# julia_v2.net
KiCad netlist of a schematic drawn in EAGLE
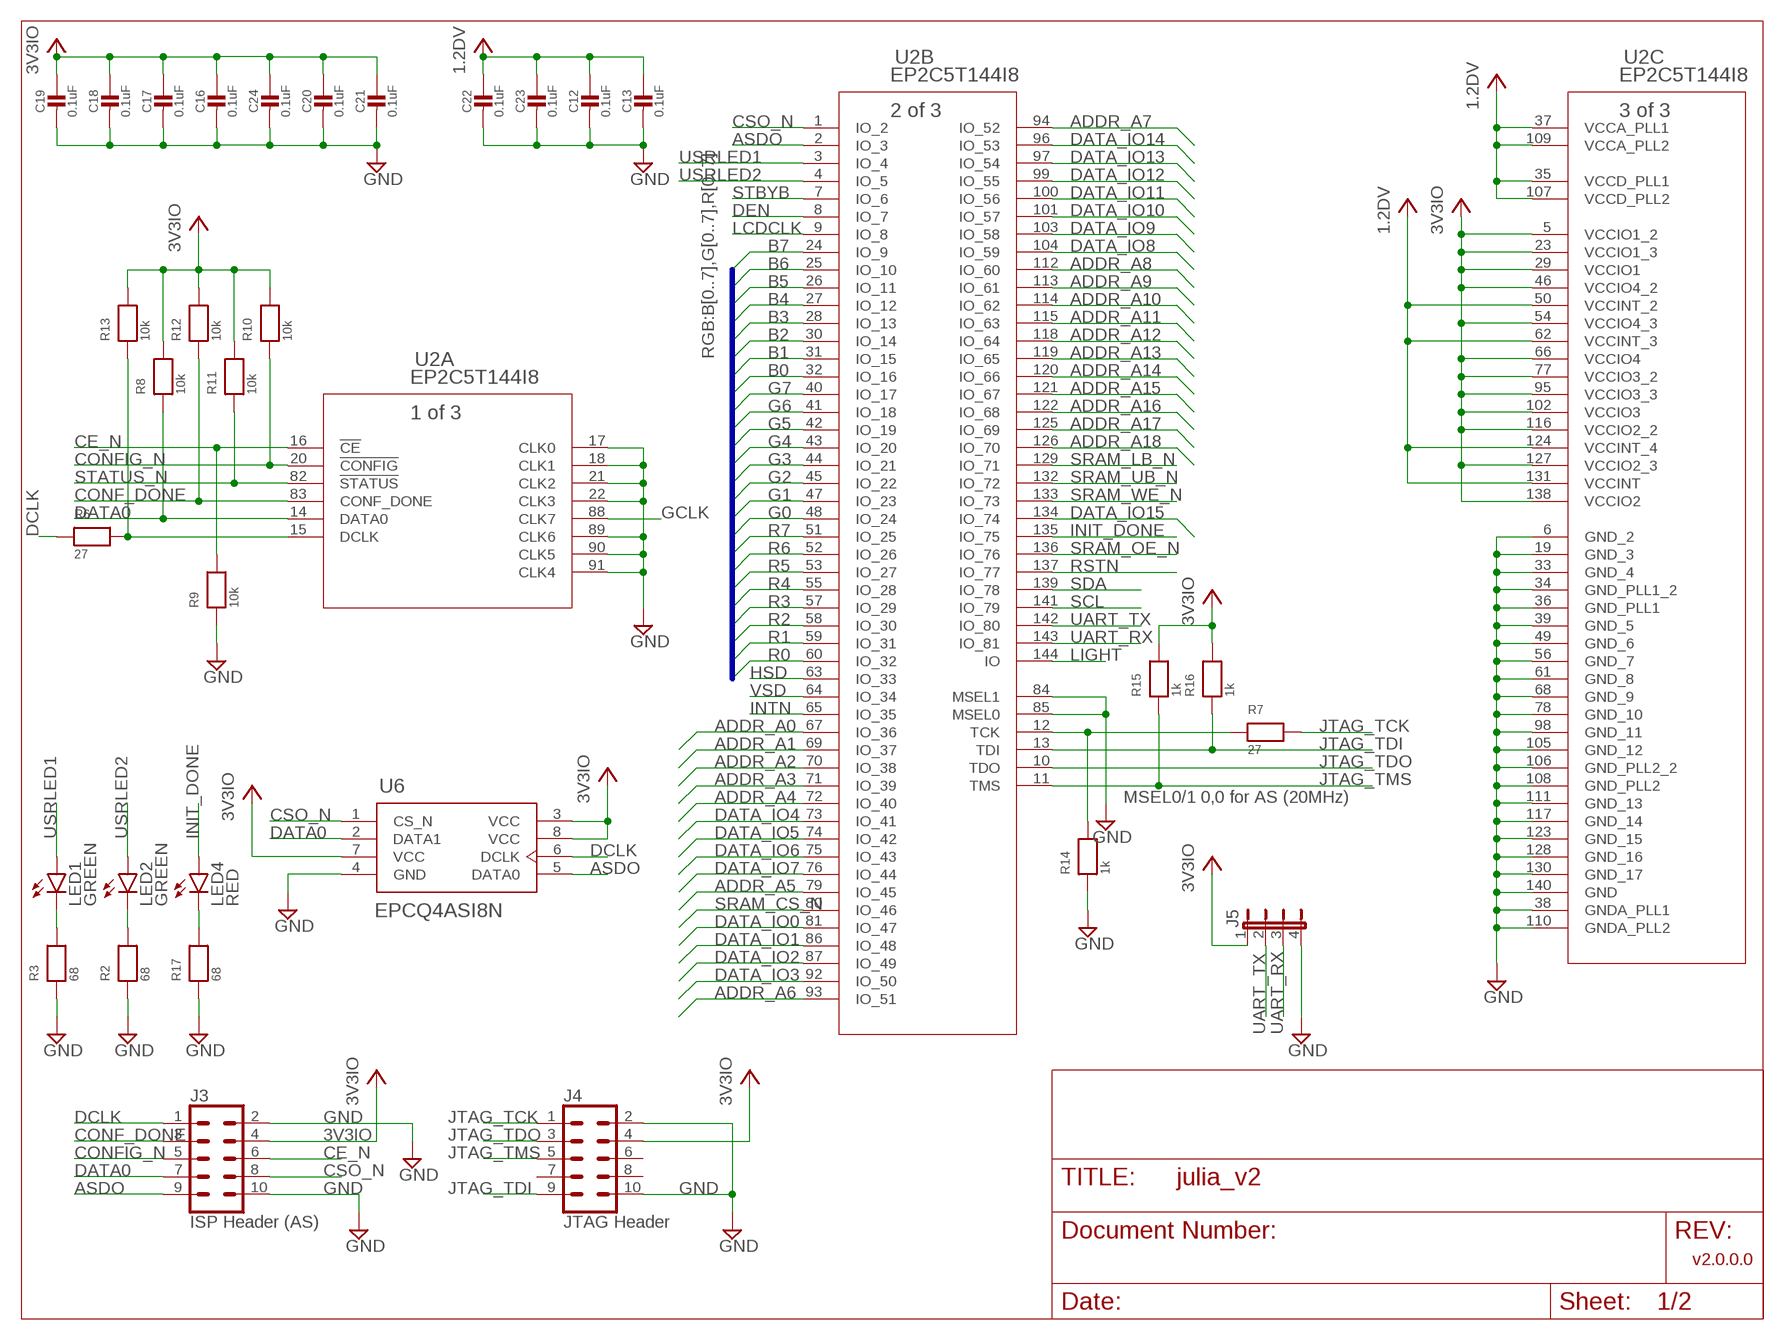
[diagram p0: schematic, sheet 1]
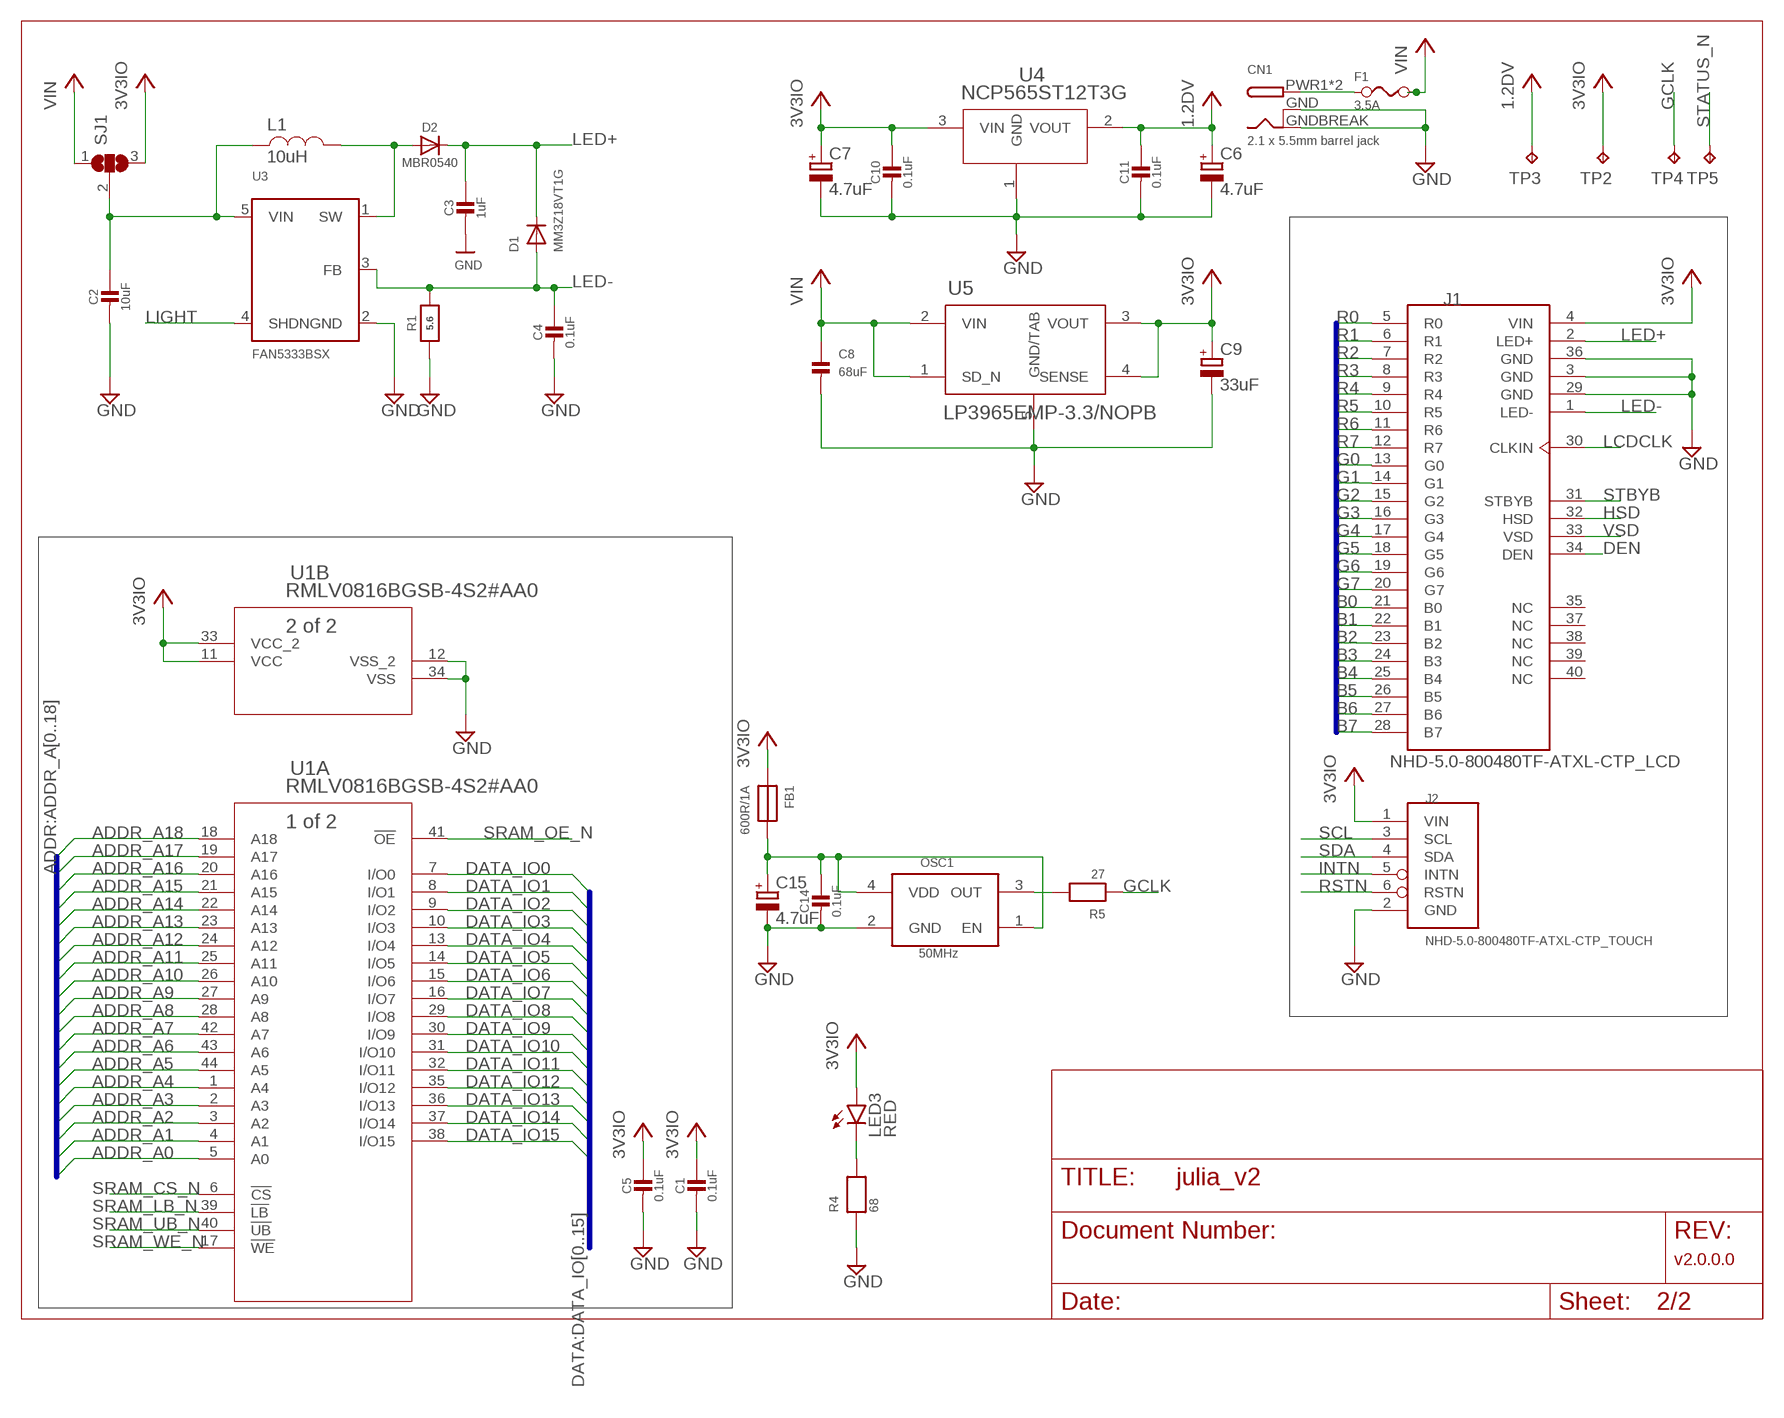
[diagram p1: schematic, sheet 2]

(export (version "E")
  (design (tool "Eeschema 10.0.6"))
  (components
    (comp (ref "C1")
      (value "0.1uF")
      (footprint "eagle-import:0805")
      (fields (field (name "MPN") "0805ZD104KAT2A"))
      (libsource (lib "eagle-import") (part "CAP_CERAMIC0805"))
    )
    (comp (ref "C2")
      (value "10uF")
      (footprint "eagle-import:0805")
      (fields (field (name "MPN") "CL21A106KPFNNNG"))
      (libsource (lib "eagle-import") (part "CAP_CERAMIC0805"))
    )
    (comp (ref "C3")
      (value "1uF")
      (footprint "eagle-import:0805")
      (fields (field (name "MPN") "CL21A105KACLNNC"))
      (libsource (lib "eagle-import") (part "CAP_CERAMIC0805"))
    )
    (comp (ref "C4")
      (value "0.1uF")
      (footprint "eagle-import:0805")
      (fields (field (name "MPN") "0805ZD104KAT2A"))
      (libsource (lib "eagle-import") (part "CAP_CERAMIC0805"))
    )
    (comp (ref "C5")
      (value "0.1uF")
      (footprint "eagle-import:0805")
      (fields (field (name "MPN") "0805ZD104KAT2A"))
      (libsource (lib "eagle-import") (part "CAP_CERAMIC0805"))
    )
    (comp (ref "C6")
      (value "4.7uF")
      (footprint "eagle-import:CPOL0805")
      (fields (field (name "MPN") "F920J475MPA"))
      (libsource (lib "eagle-import") (part "CPOL"))
    )
    (comp (ref "C7")
      (value "4.7uF")
      (footprint "eagle-import:CPOL0805")
      (fields (field (name "MPN") "F920J475MPA"))
      (libsource (lib "eagle-import") (part "CPOL"))
    )
    (comp (ref "C8")
      (value "68uF")
      (footprint "eagle-import:1206")
      (fields (field (name "MPN") "C3216X5R1A686M160AC"))
      (libsource (lib "eagle-import") (part "CAP_CERAMIC1206"))
    )
    (comp (ref "C9")
      (value "33uF")
      (footprint "eagle-import:CPOL0805")
      (fields (field (name "MPN") "TLJP336M010R3500"))
      (libsource (lib "eagle-import") (part "CPOL"))
    )
    (comp (ref "C10")
      (value "0.1uF")
      (footprint "eagle-import:0805")
      (fields (field (name "MPN") "0805ZD104KAT2A"))
      (libsource (lib "eagle-import") (part "CAP_CERAMIC0805"))
    )
    (comp (ref "C11")
      (value "0.1uF")
      (footprint "eagle-import:0805")
      (fields (field (name "MPN") "0805ZD104KAT2A"))
      (libsource (lib "eagle-import") (part "CAP_CERAMIC0805"))
    )
    (comp (ref "C14")
      (value "0.1uF")
      (footprint "eagle-import:0805")
      (fields (field (name "MPN") "0805ZD104KAT2A"))
      (libsource (lib "eagle-import") (part "CAP_CERAMIC0805"))
    )
    (comp (ref "C15")
      (value "4.7uF")
      (footprint "eagle-import:CPOL0805")
      (fields (field (name "MPN") "F920J475MPA"))
      (libsource (lib "eagle-import") (part "CPOL"))
    )
    (comp (ref "CN1")
      (value "DCBARRELSMT")
      (footprint "eagle-import:DCJACK_2MM_SMT")
      (fields (field (name "MPN") "DCJ200-05-A-K1-A"))
      (libsource (lib "eagle-import") (part "DCBARRELSMT"))
    )
    (comp (ref "D1")
      (value "MM3Z18VT1G")
      (footprint "eagle-import:SOD-323")
      (libsource (lib "eagle-import") (part "DIODE-SOD323"))
    )
    (comp (ref "D2")
      (value "MBR0540")
      (footprint "eagle-import:SOD-123")
      (libsource (lib "eagle-import") (part "DIODESOD-123"))
    )
    (comp (ref "F1")
      (value "3.5A")
      (footprint "eagle-import:1206")
      (fields (field (name "MPN") "C1F 3.5"))
      (libsource (lib "eagle-import") (part "FUSE12061206"))
    )
    (comp (ref "FB1")
      (value "600R/1A")
      (footprint "eagle-import:0603")
      (fields (field (name "MPN") "MI0603J601R-10"))
      (libsource (lib "eagle-import") (part "FERRITE"))
    )
    (comp (ref "J1")
      (value "NHD-5.0-800480TF-ATXL-CTP_LCD")
      (footprint "eagle-import:54132-4097")
      (fields (field (name "MPN") "54104-4031"))
      (libsource (lib "eagle-import") (part "NHD-5.0-800480TF-ATXL-CTP_LCD"))
    )
    (comp (ref "J2")
      (value "NHD-5.0-800480TF-ATXL-CTP_TOUCH")
      (footprint "eagle-import:52271-0679")
      (fields (field (name "MPN") "52271-0679"))
      (libsource (lib "eagle-import") (part "NHD-5.0-800480TF-ATXL-CTP_TOUCH"))
    )
    (comp (ref "L1")
      (value "10uH")
      (footprint "eagle-import:SPM10040T-100M-HZ")
      (fields (field (name "MPN") "SPM10040T-100M-HZ"))
      (libsource (lib "eagle-import") (part "SPM10040T-100M-HZ"))
    )
    (comp (ref "LED3")
      (value "RED")
      (footprint "eagle-import:CHIPLED_0805")
      (fields (field (name "MPN") "SML-LXT0805IW-TR"))
      (libsource (lib "eagle-import") (part "LEDCHIPLED_0805"))
    )
    (comp (ref "OSC1")
      (value "50MHz")
      (footprint "eagle-import:CRYSTALASV")
      (fields (field (name "MPN") "  ASV-50.000MHZ-EJ-T"))
      (libsource (lib "eagle-import") (part "ASV-50.000MHZ-EJ-T"))
    )
    (comp (ref "R1")
      (value "5.6")
      (footprint "eagle-import:0805")
      (fields (field (name "MPN") "RC0805FR-075R6L"))
      (libsource (lib "eagle-import") (part "RESISTOR0805"))
    )
    (comp (ref "R4")
      (value "68")
      (footprint "eagle-import:0805")
      (fields (field (name "MPN") "RC0805FR-0768RL"))
      (libsource (lib "eagle-import") (part "RESISTOR0805"))
    )
    (comp (ref "R5")
      (value "27")
      (footprint "eagle-import:0805")
      (fields (field (name "MPN") "RC0805JR-0727RL"))
      (libsource (lib "eagle-import") (part "RESISTOR0805"))
    )
    (comp (ref "SJ1")
      (value "SJ2WW")
      (footprint "eagle-import:SJ_2W")
      (libsource (lib "eagle-import") (part "SJ2WW"))
    )
    (comp (ref "TP2")
      (value "TPB1,27")
      (footprint "eagle-import:B1,27")
      (libsource (lib "eagle-import") (part "TPB1,27"))
    )
    (comp (ref "TP3")
      (value "TPB1,27")
      (footprint "eagle-import:B1,27")
      (libsource (lib "eagle-import") (part "TPB1,27"))
    )
    (comp (ref "TP4")
      (value "TPB1,27")
      (footprint "eagle-import:B1,27")
      (libsource (lib "eagle-import") (part "TPB1,27"))
    )
    (comp (ref "TP5")
      (value "TPB1,27")
      (footprint "eagle-import:B1,27")
      (libsource (lib "eagle-import") (part "TPB1,27"))
    )
    (comp (ref "U1")
      (value "RMLV0816BGSB-4S2#AA0")
      (footprint "eagle-import:PTSB0044GG-A_REN")
      (libsource (lib "eagle-import") (part "RMLV0816BGSB-4S2#AA0"))
    )
    (comp (ref "U3")
      (value "FAN5333BSX")
      (footprint "eagle-import:SOT23-5@1")
      (libsource (lib "eagle-import") (part "FAN5331"))
    )
    (comp (ref "U4")
      (value "NCP565ST12T3G")
      (footprint "eagle-import:SOT223-3_ONS")
      (libsource (lib "eagle-import") (part "NCP565ST12T3G"))
    )
    (comp (ref "U5")
      (value "LP3965EMP-3.3/NOPB")
      (footprint "eagle-import:NDC0005A")
      (libsource (lib "eagle-import") (part "LP3965EMP-3.3/NOPB"))
    )
    (comp (ref "C12")
      (value "0.1uF")
      (footprint "eagle-import:0805")
      (fields (field (name "MPN") "0805ZD104KAT2A"))
      (libsource (lib "eagle-import") (part "CAP_CERAMIC0805"))
    )
    (comp (ref "C13")
      (value "0.1uF")
      (footprint "eagle-import:0805")
      (fields (field (name "MPN") "0805ZD104KAT2A"))
      (libsource (lib "eagle-import") (part "CAP_CERAMIC0805"))
    )
    (comp (ref "C16")
      (value "0.1uF")
      (footprint "eagle-import:0805")
      (fields (field (name "MPN") "0805ZD104KAT2A"))
      (libsource (lib "eagle-import") (part "CAP_CERAMIC0805"))
    )
    (comp (ref "C17")
      (value "0.1uF")
      (footprint "eagle-import:0805")
      (fields (field (name "MPN") "0805ZD104KAT2A"))
      (libsource (lib "eagle-import") (part "CAP_CERAMIC0805"))
    )
    (comp (ref "C18")
      (value "0.1uF")
      (footprint "eagle-import:0805")
      (fields (field (name "MPN") "0805ZD104KAT2A"))
      (libsource (lib "eagle-import") (part "CAP_CERAMIC0805"))
    )
    (comp (ref "C19")
      (value "0.1uF")
      (footprint "eagle-import:0805")
      (fields (field (name "MPN") "0805ZD104KAT2A"))
      (libsource (lib "eagle-import") (part "CAP_CERAMIC0805"))
    )
    (comp (ref "C20")
      (value "0.1uF")
      (footprint "eagle-import:0805")
      (fields (field (name "MPN") "0805ZD104KAT2A"))
      (libsource (lib "eagle-import") (part "CAP_CERAMIC0805"))
    )
    (comp (ref "C21")
      (value "0.1uF")
      (footprint "eagle-import:0805")
      (fields (field (name "MPN") "0805ZD104KAT2A"))
      (libsource (lib "eagle-import") (part "CAP_CERAMIC0805"))
    )
    (comp (ref "C22")
      (value "0.1uF")
      (footprint "eagle-import:0805")
      (fields (field (name "MPN") "0805ZD104KAT2A"))
      (libsource (lib "eagle-import") (part "CAP_CERAMIC0805"))
    )
    (comp (ref "C23")
      (value "0.1uF")
      (footprint "eagle-import:0805")
      (fields (field (name "MPN") "0805ZD104KAT2A"))
      (libsource (lib "eagle-import") (part "CAP_CERAMIC0805"))
    )
    (comp (ref "C24")
      (value "0.1uF")
      (footprint "eagle-import:0805")
      (fields (field (name "MPN") "0805ZD104KAT2A"))
      (libsource (lib "eagle-import") (part "CAP_CERAMIC0805"))
    )
    (comp (ref "J3")
      (value "ISP Header (AS)")
      (footprint "eagle-import:2X5-SHROUDED")
      (fields (field (name "MPN") "SBH11-PBPC-D05-ST-BK"))
      (libsource (lib "eagle-import") (part "CONN_05X2SHD"))
    )
    (comp (ref "J4")
      (value "JTAG Header")
      (footprint "eagle-import:2X5-SHROUDED")
      (fields (field (name "MPN") "SBH11-PBPC-D05-ST-BK"))
      (libsource (lib "eagle-import") (part "CONN_05X2SHD"))
    )
    (comp (ref "J5")
      (value "JP4E")
      (footprint "eagle-import:JP4")
      (libsource (lib "eagle-import") (part "JP4E"))
    )
    (comp (ref "LED1")
      (value "GREEN")
      (footprint "eagle-import:CHIPLED_0805")
      (fields (field (name "MPN") "ML-LXT0805IW-TR"))
      (libsource (lib "eagle-import") (part "LEDCHIPLED_0805"))
    )
    (comp (ref "LED2")
      (value "GREEN")
      (footprint "eagle-import:CHIPLED_0805")
      (fields (field (name "MPN") "ML-LXT0805IW-TR"))
      (libsource (lib "eagle-import") (part "LEDCHIPLED_0805"))
    )
    (comp (ref "LED4")
      (value "RED")
      (footprint "eagle-import:CHIPLED_0805")
      (fields (field (name "MPN") "SML-LXT0805IW-TR"))
      (libsource (lib "eagle-import") (part "LEDCHIPLED_0805"))
    )
    (comp (ref "R2")
      (value "68")
      (footprint "eagle-import:0805")
      (fields (field (name "MPN") "RC0805FR-0768RL"))
      (libsource (lib "eagle-import") (part "RESISTOR0805"))
    )
    (comp (ref "R3")
      (value "68")
      (footprint "eagle-import:0805")
      (fields (field (name "MPN") "RC0805FR-0768RL"))
      (libsource (lib "eagle-import") (part "RESISTOR0805"))
    )
    (comp (ref "R6")
      (value "27")
      (footprint "eagle-import:0805")
      (fields (field (name "MPN") "RC0805JR-0727RL"))
      (libsource (lib "eagle-import") (part "RESISTOR0805"))
    )
    (comp (ref "R7")
      (value "27")
      (footprint "eagle-import:0805")
      (fields (field (name "MPN") "RC0805JR-0727RL"))
      (libsource (lib "eagle-import") (part "RESISTOR0805"))
    )
    (comp (ref "R8")
      (value "10k")
      (footprint "eagle-import:0805")
      (fields (field (name "MPN") "RC0805FR-0710KL"))
      (libsource (lib "eagle-import") (part "RESISTOR0805"))
    )
    (comp (ref "R9")
      (value "10k")
      (footprint "eagle-import:0805")
      (fields (field (name "MPN") "RC0805FR-0710KL"))
      (libsource (lib "eagle-import") (part "RESISTOR0805"))
    )
    (comp (ref "R10")
      (value "10k")
      (footprint "eagle-import:0805")
      (fields (field (name "MPN") "RC0805FR-0710KL"))
      (libsource (lib "eagle-import") (part "RESISTOR0805"))
    )
    (comp (ref "R11")
      (value "10k")
      (footprint "eagle-import:0805")
      (fields (field (name "MPN") "RC0805FR-0710KL"))
      (libsource (lib "eagle-import") (part "RESISTOR0805"))
    )
    (comp (ref "R12")
      (value "10k")
      (footprint "eagle-import:0805")
      (fields (field (name "MPN") "RC0805FR-0710KL"))
      (libsource (lib "eagle-import") (part "RESISTOR0805"))
    )
    (comp (ref "R13")
      (value "10k")
      (footprint "eagle-import:0805")
      (fields (field (name "MPN") "RC0805FR-0710KL"))
      (libsource (lib "eagle-import") (part "RESISTOR0805"))
    )
    (comp (ref "R14")
      (value "1k")
      (footprint "eagle-import:0805")
      (fields (field (name "MPN") "RC0805FR-071KL"))
      (libsource (lib "eagle-import") (part "RESISTOR0805"))
    )
    (comp (ref "R15")
      (value "1k")
      (footprint "eagle-import:0805")
      (fields (field (name "MPN") "RC0805FR-071KL"))
      (libsource (lib "eagle-import") (part "RESISTOR0805"))
    )
    (comp (ref "R16")
      (value "1k")
      (footprint "eagle-import:0805")
      (fields (field (name "MPN") "RC0805FR-071KL"))
      (libsource (lib "eagle-import") (part "RESISTOR0805"))
    )
    (comp (ref "R17")
      (value "68")
      (footprint "eagle-import:0805")
      (fields (field (name "MPN") "RC0805FR-0768RL"))
      (libsource (lib "eagle-import") (part "RESISTOR0805"))
    )
    (comp (ref "U2")
      (value "EP2C5T144I8")
      (footprint "eagle-import:144-TQFP_ALR")
      (fields (field (name "DPN") "544-2138-ND") (field (name "MPN") "EP2C5T144I8"))
      (libsource (lib "eagle-import") (part "EP2C5T144I8"))
    )
    (comp (ref "U6")
      (value "EPCQ4ASI8N")
      (footprint "eagle-import:8SOIC")
      (libsource (lib "eagle-import") (part "EPCQ4ASI8N"))
    )
  )
  (nets
    (net (code "39") (name "1.2DV") (class "Default")
      (node (ref "C11") (pin "1") (pinfunction "P$1_1") (pintype "passive"))
      (node (ref "C12") (pin "1") (pinfunction "P$1_1") (pintype "passive"))
      (node (ref "C13") (pin "1") (pinfunction "P$1_1") (pintype "passive"))
      (node (ref "C22") (pin "1") (pinfunction "P$1_1") (pintype "passive"))
      (node (ref "C23") (pin "1") (pinfunction "P$1_1") (pintype "passive"))
      (node (ref "C6") (pin "1") (pinfunction "+_1") (pintype "passive"))
      (node (ref "TP3") (pin "TP") (pinfunction "TP_TP") (pintype "input"))
      (node (ref "U2") (pin "107") (pinfunction "VCCD_PLL2_107") (pintype "passive"))
      (node (ref "U2") (pin "109") (pinfunction "VCCA_PLL2_109") (pintype "passive"))
      (node (ref "U2") (pin "124") (pinfunction "VCCINT_4_124") (pintype "passive"))
      (node (ref "U2") (pin "131") (pinfunction "VCCINT_131") (pintype "passive"))
      (node (ref "U2") (pin "35") (pinfunction "VCCD_PLL1_35") (pintype "passive"))
      (node (ref "U2") (pin "37") (pinfunction "VCCA_PLL1_37") (pintype "passive"))
      (node (ref "U2") (pin "50") (pinfunction "VCCINT_2_50") (pintype "passive"))
      (node (ref "U2") (pin "62") (pinfunction "VCCINT_3_62") (pintype "passive"))
      (node (ref "U4") (pin "2") (pinfunction "VOUT_2") (pintype "power_in"))
    )
    (net (code "40") (name "3V3IO") (class "Default")
      (node (ref "C1") (pin "1") (pinfunction "P$1_1") (pintype "passive"))
      (node (ref "C10") (pin "1") (pinfunction "P$1_1") (pintype "passive"))
      (node (ref "C16") (pin "1") (pinfunction "P$1_1") (pintype "passive"))
      (node (ref "C17") (pin "1") (pinfunction "P$1_1") (pintype "passive"))
      (node (ref "C18") (pin "1") (pinfunction "P$1_1") (pintype "passive"))
      (node (ref "C19") (pin "1") (pinfunction "P$1_1") (pintype "passive"))
      (node (ref "C20") (pin "1") (pinfunction "P$1_1") (pintype "passive"))
      (node (ref "C21") (pin "1") (pinfunction "P$1_1") (pintype "passive"))
      (node (ref "C24") (pin "1") (pinfunction "P$1_1") (pintype "passive"))
      (node (ref "C5") (pin "1") (pinfunction "P$1_1") (pintype "passive"))
      (node (ref "C7") (pin "1") (pinfunction "+_1") (pintype "passive"))
      (node (ref "C9") (pin "1") (pinfunction "+_1") (pintype "passive"))
      (node (ref "FB1") (pin "1") (pinfunction "P$1_1") (pintype "bidirectional"))
      (node (ref "J1") (pin "4") (pinfunction "VIN_4") (pintype "power_in"))
      (node (ref "J2") (pin "1") (pinfunction "VIN_1") (pintype "power_in"))
      (node (ref "J3") (pin "4") (pinfunction "4_4") (pintype "passive"))
      (node (ref "J4") (pin "4") (pinfunction "4_4") (pintype "passive"))
      (node (ref "J5") (pin "1") (pinfunction "1_1") (pintype "passive"))
      (node (ref "LED3") (pin "A") (pinfunction "A_A") (pintype "passive"))
      (node (ref "R10") (pin "2") (pinfunction "2_2") (pintype "passive"))
      (node (ref "R11") (pin "2") (pinfunction "2_2") (pintype "passive"))
      (node (ref "R12") (pin "2") (pinfunction "2_2") (pintype "passive"))
      (node (ref "R13") (pin "2") (pinfunction "2_2") (pintype "passive"))
      (node (ref "R15") (pin "2") (pinfunction "2_2") (pintype "passive"))
      (node (ref "R16") (pin "2") (pinfunction "2_2") (pintype "passive"))
      (node (ref "R8") (pin "2") (pinfunction "2_2") (pintype "passive"))
      (node (ref "SJ1") (pin "3") (pinfunction "3_3") (pintype "passive"))
      (node (ref "TP2") (pin "TP") (pinfunction "TP_TP") (pintype "input"))
      (node (ref "U1") (pin "11") (pinfunction "VCC_11") (pintype "power_in"))
      (node (ref "U1") (pin "33") (pinfunction "VCC_2_33") (pintype "power_in"))
      (node (ref "U2") (pin "102") (pinfunction "VCCIO3_102") (pintype "passive"))
      (node (ref "U2") (pin "116") (pinfunction "VCCIO2_2_116") (pintype "passive"))
      (node (ref "U2") (pin "127") (pinfunction "VCCIO2_3_127") (pintype "passive"))
      (node (ref "U2") (pin "138") (pinfunction "VCCIO2_138") (pintype "passive"))
      (node (ref "U2") (pin "23") (pinfunction "VCCIO1_3_23") (pintype "passive"))
      (node (ref "U2") (pin "29") (pinfunction "VCCIO1_29") (pintype "passive"))
      (node (ref "U2") (pin "46") (pinfunction "VCCIO4_2_46") (pintype "passive"))
      (node (ref "U2") (pin "5") (pinfunction "VCCIO1_2_5") (pintype "passive"))
      (node (ref "U2") (pin "54") (pinfunction "VCCIO4_3_54") (pintype "passive"))
      (node (ref "U2") (pin "66") (pinfunction "VCCIO4_66") (pintype "passive"))
      (node (ref "U2") (pin "77") (pinfunction "VCCIO3_2_77") (pintype "passive"))
      (node (ref "U2") (pin "95") (pinfunction "VCCIO3_3_95") (pintype "passive"))
      (node (ref "U4") (pin "3") (pinfunction "VIN_3") (pintype "power_in"))
      (node (ref "U5") (pin "3") (pinfunction "VOUT_3") (pintype "power_in"))
      (node (ref "U5") (pin "4") (pinfunction "SENSE_4") (pintype "input"))
      (node (ref "U6") (pin "3") (pinfunction "VCC_3") (pintype "power_in"))
      (node (ref "U6") (pin "7") (pinfunction "VCC_7") (pintype "power_in"))
      (node (ref "U6") (pin "8") (pinfunction "VCC_8") (pintype "power_in"))
    )
    (net (code "41") (name "ADDR_A0") (class "Default")
      (node (ref "U1") (pin "5") (pinfunction "A0_5") (pintype "input"))
      (node (ref "U2") (pin "67") (pinfunction "IO_36_67") (pintype "passive"))
    )
    (net (code "42") (name "ADDR_A1") (class "Default")
      (node (ref "U1") (pin "4") (pinfunction "A1_4") (pintype "input"))
      (node (ref "U2") (pin "69") (pinfunction "IO_37_69") (pintype "passive"))
    )
    (net (code "43") (name "ADDR_A2") (class "Default")
      (node (ref "U1") (pin "3") (pinfunction "A2_3") (pintype "input"))
      (node (ref "U2") (pin "70") (pinfunction "IO_38_70") (pintype "passive"))
    )
    (net (code "44") (name "ADDR_A3") (class "Default")
      (node (ref "U1") (pin "2") (pinfunction "A3_2") (pintype "input"))
      (node (ref "U2") (pin "71") (pinfunction "IO_39_71") (pintype "passive"))
    )
    (net (code "45") (name "ADDR_A4") (class "Default")
      (node (ref "U1") (pin "1") (pinfunction "A4_1") (pintype "input"))
      (node (ref "U2") (pin "72") (pinfunction "IO_40_72") (pintype "passive"))
    )
    (net (code "46") (name "ADDR_A5") (class "Default")
      (node (ref "U1") (pin "44") (pinfunction "A5_44") (pintype "input"))
      (node (ref "U2") (pin "79") (pinfunction "IO_45_79") (pintype "passive"))
    )
    (net (code "47") (name "ADDR_A6") (class "Default")
      (node (ref "U1") (pin "43") (pinfunction "A6_43") (pintype "input"))
      (node (ref "U2") (pin "93") (pinfunction "IO_51_93") (pintype "passive"))
    )
    (net (code "48") (name "ADDR_A7") (class "Default")
      (node (ref "U1") (pin "42") (pinfunction "A7_42") (pintype "input"))
      (node (ref "U2") (pin "94") (pinfunction "IO_52_94") (pintype "passive"))
    )
    (net (code "49") (name "ADDR_A8") (class "Default")
      (node (ref "U1") (pin "28") (pinfunction "A8_28") (pintype "input"))
      (node (ref "U2") (pin "112") (pinfunction "IO_60_112") (pintype "passive"))
    )
    (net (code "50") (name "ADDR_A9") (class "Default")
      (node (ref "U1") (pin "27") (pinfunction "A9_27") (pintype "input"))
      (node (ref "U2") (pin "113") (pinfunction "IO_61_113") (pintype "passive"))
    )
    (net (code "51") (name "ADDR_A10") (class "Default")
      (node (ref "U1") (pin "26") (pinfunction "A10_26") (pintype "input"))
      (node (ref "U2") (pin "114") (pinfunction "IO_62_114") (pintype "passive"))
    )
    (net (code "52") (name "ADDR_A11") (class "Default")
      (node (ref "U1") (pin "25") (pinfunction "A11_25") (pintype "input"))
      (node (ref "U2") (pin "115") (pinfunction "IO_63_115") (pintype "passive"))
    )
    (net (code "53") (name "ADDR_A12") (class "Default")
      (node (ref "U1") (pin "24") (pinfunction "A12_24") (pintype "input"))
      (node (ref "U2") (pin "118") (pinfunction "IO_64_118") (pintype "passive"))
    )
    (net (code "54") (name "ADDR_A13") (class "Default")
      (node (ref "U1") (pin "23") (pinfunction "A13_23") (pintype "input"))
      (node (ref "U2") (pin "119") (pinfunction "IO_65_119") (pintype "passive"))
    )
    (net (code "55") (name "ADDR_A14") (class "Default")
      (node (ref "U1") (pin "22") (pinfunction "A14_22") (pintype "input"))
      (node (ref "U2") (pin "120") (pinfunction "IO_66_120") (pintype "passive"))
    )
    (net (code "56") (name "ADDR_A15") (class "Default")
      (node (ref "U1") (pin "21") (pinfunction "A15_21") (pintype "input"))
      (node (ref "U2") (pin "121") (pinfunction "IO_67_121") (pintype "passive"))
    )
    (net (code "57") (name "ADDR_A16") (class "Default")
      (node (ref "U1") (pin "20") (pinfunction "A16_20") (pintype "input"))
      (node (ref "U2") (pin "122") (pinfunction "IO_68_122") (pintype "passive"))
    )
    (net (code "58") (name "ADDR_A17") (class "Default")
      (node (ref "U1") (pin "19") (pinfunction "A17_19") (pintype "input"))
      (node (ref "U2") (pin "125") (pinfunction "IO_69_125") (pintype "passive"))
    )
    (net (code "59") (name "ADDR_A18") (class "Default")
      (node (ref "U1") (pin "18") (pinfunction "A18_18") (pintype "input"))
      (node (ref "U2") (pin "126") (pinfunction "IO_70_126") (pintype "passive"))
    )
    (net (code "60") (name "ASDO") (class "Default")
      (node (ref "J3") (pin "9") (pinfunction "9_9") (pintype "passive"))
      (node (ref "U2") (pin "2") (pinfunction "IO_3_2") (pintype "passive"))
      (node (ref "U6") (pin "5") (pinfunction "DATA0_5") (pintype "input"))
    )
    (net (code "61") (name "B0") (class "Default")
      (node (ref "J1") (pin "21") (pinfunction "B0_21") (pintype "input"))
      (node (ref "U2") (pin "32") (pinfunction "IO_16_32") (pintype "passive"))
    )
    (net (code "62") (name "B1") (class "Default")
      (node (ref "J1") (pin "22") (pinfunction "B1_22") (pintype "input"))
      (node (ref "U2") (pin "31") (pinfunction "IO_15_31") (pintype "passive"))
    )
    (net (code "63") (name "B2") (class "Default")
      (node (ref "J1") (pin "23") (pinfunction "B2_23") (pintype "input"))
      (node (ref "U2") (pin "30") (pinfunction "IO_14_30") (pintype "passive"))
    )
    (net (code "64") (name "B3") (class "Default")
      (node (ref "J1") (pin "24") (pinfunction "B3_24") (pintype "input"))
      (node (ref "U2") (pin "28") (pinfunction "IO_13_28") (pintype "passive"))
    )
    (net (code "65") (name "B4") (class "Default")
      (node (ref "J1") (pin "25") (pinfunction "B4_25") (pintype "input"))
      (node (ref "U2") (pin "27") (pinfunction "IO_12_27") (pintype "passive"))
    )
    (net (code "66") (name "B5") (class "Default")
      (node (ref "J1") (pin "26") (pinfunction "B5_26") (pintype "input"))
      (node (ref "U2") (pin "26") (pinfunction "IO_11_26") (pintype "passive"))
    )
    (net (code "67") (name "B6") (class "Default")
      (node (ref "J1") (pin "27") (pinfunction "B6_27") (pintype "input"))
      (node (ref "U2") (pin "25") (pinfunction "IO_10_25") (pintype "passive"))
    )
    (net (code "68") (name "B7") (class "Default")
      (node (ref "J1") (pin "28") (pinfunction "B7_28") (pintype "input"))
      (node (ref "U2") (pin "24") (pinfunction "IO_9_24") (pintype "passive"))
    )
    (net (code "69") (name "CE_N") (class "Default")
      (node (ref "J3") (pin "6") (pinfunction "6_6") (pintype "passive"))
      (node (ref "R9") (pin "2") (pinfunction "2_2") (pintype "passive"))
      (node (ref "U2") (pin "16") (pinfunction "~{CE}_16") (pintype "passive"))
    )
    (net (code "70") (name "CONFIG_N") (class "Default")
      (node (ref "J3") (pin "5") (pinfunction "5_5") (pintype "passive"))
      (node (ref "R10") (pin "1") (pinfunction "1_1") (pintype "passive"))
      (node (ref "U2") (pin "20") (pinfunction "~{CONFIG}_20") (pintype "passive"))
    )
    (net (code "71") (name "CONF_DONE") (class "Default")
      (node (ref "J3") (pin "3") (pinfunction "3_3") (pintype "passive"))
      (node (ref "R12") (pin "1") (pinfunction "1_1") (pintype "passive"))
      (node (ref "U2") (pin "83") (pinfunction "CONF_DONE_83") (pintype "passive"))
    )
    (net (code "72") (name "CSO_N") (class "Default")
      (node (ref "J3") (pin "8") (pinfunction "8_8") (pintype "passive"))
      (node (ref "U2") (pin "1") (pinfunction "IO_2_1") (pintype "passive"))
      (node (ref "U6") (pin "1") (pinfunction "CS_N_1") (pintype "input"))
    )
    (net (code "73") (name "DATA0") (class "Default")
      (node (ref "J3") (pin "7") (pinfunction "7_7") (pintype "passive"))
      (node (ref "R8") (pin "1") (pinfunction "1_1") (pintype "passive"))
      (node (ref "U2") (pin "14") (pinfunction "DATA0_14") (pintype "passive"))
      (node (ref "U6") (pin "2") (pinfunction "DATA1_2") (pintype "output"))
    )
    (net (code "74") (name "DATA_IO0") (class "Default")
      (node (ref "U1") (pin "7") (pinfunction "I/O0_7") (pintype "bidirectional"))
      (node (ref "U2") (pin "81") (pinfunction "IO_47_81") (pintype "passive"))
    )
    (net (code "75") (name "DATA_IO1") (class "Default")
      (node (ref "U1") (pin "8") (pinfunction "I/O1_8") (pintype "bidirectional"))
      (node (ref "U2") (pin "86") (pinfunction "IO_48_86") (pintype "passive"))
    )
    (net (code "76") (name "DATA_IO2") (class "Default")
      (node (ref "U1") (pin "9") (pinfunction "I/O2_9") (pintype "bidirectional"))
      (node (ref "U2") (pin "87") (pinfunction "IO_49_87") (pintype "passive"))
    )
    (net (code "77") (name "DATA_IO3") (class "Default")
      (node (ref "U1") (pin "10") (pinfunction "I/O3_10") (pintype "bidirectional"))
      (node (ref "U2") (pin "92") (pinfunction "IO_50_92") (pintype "passive"))
    )
    (net (code "78") (name "DATA_IO4") (class "Default")
      (node (ref "U1") (pin "13") (pinfunction "I/O4_13") (pintype "bidirectional"))
      (node (ref "U2") (pin "73") (pinfunction "IO_41_73") (pintype "passive"))
    )
    (net (code "79") (name "DATA_IO5") (class "Default")
      (node (ref "U1") (pin "14") (pinfunction "I/O5_14") (pintype "bidirectional"))
      (node (ref "U2") (pin "74") (pinfunction "IO_42_74") (pintype "passive"))
    )
    (net (code "80") (name "DATA_IO6") (class "Default")
      (node (ref "U1") (pin "15") (pinfunction "I/O6_15") (pintype "bidirectional"))
      (node (ref "U2") (pin "75") (pinfunction "IO_43_75") (pintype "passive"))
    )
    (net (code "81") (name "DATA_IO7") (class "Default")
      (node (ref "U1") (pin "16") (pinfunction "I/O7_16") (pintype "bidirectional"))
      (node (ref "U2") (pin "76") (pinfunction "IO_44_76") (pintype "passive"))
    )
    (net (code "82") (name "DATA_IO8") (class "Default")
      (node (ref "U1") (pin "29") (pinfunction "I/O8_29") (pintype "bidirectional"))
      (node (ref "U2") (pin "104") (pinfunction "IO_59_104") (pintype "passive"))
    )
    (net (code "83") (name "DATA_IO9") (class "Default")
      (node (ref "U1") (pin "30") (pinfunction "I/O9_30") (pintype "bidirectional"))
      (node (ref "U2") (pin "103") (pinfunction "IO_58_103") (pintype "passive"))
    )
    (net (code "84") (name "DATA_IO10") (class "Default")
      (node (ref "U1") (pin "31") (pinfunction "I/O10_31") (pintype "bidirectional"))
      (node (ref "U2") (pin "101") (pinfunction "IO_57_101") (pintype "passive"))
    )
    (net (code "85") (name "DATA_IO11") (class "Default")
      (node (ref "U1") (pin "32") (pinfunction "I/O11_32") (pintype "bidirectional"))
      (node (ref "U2") (pin "100") (pinfunction "IO_56_100") (pintype "passive"))
    )
    (net (code "86") (name "DATA_IO12") (class "Default")
      (node (ref "U1") (pin "35") (pinfunction "I/O12_35") (pintype "bidirectional"))
      (node (ref "U2") (pin "99") (pinfunction "IO_55_99") (pintype "passive"))
    )
    (net (code "87") (name "DATA_IO13") (class "Default")
      (node (ref "U1") (pin "36") (pinfunction "I/O13_36") (pintype "bidirectional"))
      (node (ref "U2") (pin "97") (pinfunction "IO_54_97") (pintype "passive"))
    )
    (net (code "88") (name "DATA_IO14") (class "Default")
      (node (ref "U1") (pin "37") (pinfunction "I/O14_37") (pintype "bidirectional"))
      (node (ref "U2") (pin "96") (pinfunction "IO_53_96") (pintype "passive"))
    )
    (net (code "89") (name "DATA_IO15") (class "Default")
      (node (ref "U1") (pin "38") (pinfunction "I/O15_38") (pintype "bidirectional"))
      (node (ref "U2") (pin "134") (pinfunction "IO_74_134") (pintype "passive"))
    )
    (net (code "90") (name "DCLK") (class "Default")
      (node (ref "J3") (pin "1") (pinfunction "1_1") (pintype "passive"))
      (node (ref "R6") (pin "1") (pinfunction "1_1") (pintype "passive"))
      (node (ref "U6") (pin "6") (pinfunction "DCLK_6") (pintype "input"))
    )
    (net (code "91") (name "DEN") (class "Default")
      (node (ref "J1") (pin "34") (pinfunction "DEN_34") (pintype "input"))
      (node (ref "U2") (pin "8") (pinfunction "IO_7_8") (pintype "passive"))
    )
    (net (code "92") (name "G0") (class "Default")
      (node (ref "J1") (pin "13") (pinfunction "G0_13") (pintype "input"))
      (node (ref "U2") (pin "48") (pinfunction "IO_24_48") (pintype "passive"))
    )
    (net (code "93") (name "G1") (class "Default")
      (node (ref "J1") (pin "14") (pinfunction "G1_14") (pintype "input"))
      (node (ref "U2") (pin "47") (pinfunction "IO_23_47") (pintype "passive"))
    )
    (net (code "94") (name "G2") (class "Default")
      (node (ref "J1") (pin "15") (pinfunction "G2_15") (pintype "input"))
      (node (ref "U2") (pin "45") (pinfunction "IO_22_45") (pintype "passive"))
    )
    (net (code "95") (name "G3") (class "Default")
      (node (ref "J1") (pin "16") (pinfunction "G3_16") (pintype "input"))
      (node (ref "U2") (pin "44") (pinfunction "IO_21_44") (pintype "passive"))
    )
    (net (code "96") (name "G4") (class "Default")
      (node (ref "J1") (pin "17") (pinfunction "G4_17") (pintype "input"))
      (node (ref "U2") (pin "43") (pinfunction "IO_20_43") (pintype "passive"))
    )
    (net (code "97") (name "G5") (class "Default")
      (node (ref "J1") (pin "18") (pinfunction "G5_18") (pintype "input"))
      (node (ref "U2") (pin "42") (pinfunction "IO_19_42") (pintype "passive"))
    )
    (net (code "98") (name "G6") (class "Default")
      (node (ref "J1") (pin "19") (pinfunction "G6_19") (pintype "input"))
      (node (ref "U2") (pin "41") (pinfunction "IO_18_41") (pintype "passive"))
    )
    (net (code "99") (name "G7") (class "Default")
      (node (ref "J1") (pin "20") (pinfunction "G7_20") (pintype "input"))
      (node (ref "U2") (pin "40") (pinfunction "IO_17_40") (pintype "passive"))
    )
    (net (code "100") (name "GCLK") (class "Default")
      (node (ref "R5") (pin "1") (pinfunction "1_1") (pintype "passive"))
      (node (ref "TP4") (pin "TP") (pinfunction "TP_TP") (pintype "input"))
      (node (ref "U2") (pin "88") (pinfunction "CLK7_88") (pintype "passive"))
    )
    (net (code "101") (name "GND") (class "Default")
      (node (ref "C1") (pin "2") (pinfunction "P$2_2") (pintype "passive"))
      (node (ref "C10") (pin "2") (pinfunction "P$2_2") (pintype "passive"))
      (node (ref "C11") (pin "2") (pinfunction "P$2_2") (pintype "passive"))
      (node (ref "C12") (pin "2") (pinfunction "P$2_2") (pintype "passive"))
      (node (ref "C13") (pin "2") (pinfunction "P$2_2") (pintype "passive"))
      (node (ref "C14") (pin "2") (pinfunction "P$2_2") (pintype "passive"))
      (node (ref "C15") (pin "2") (pinfunction "-_2") (pintype "passive"))
      (node (ref "C16") (pin "2") (pinfunction "P$2_2") (pintype "passive"))
      (node (ref "C17") (pin "2") (pinfunction "P$2_2") (pintype "passive"))
      (node (ref "C18") (pin "2") (pinfunction "P$2_2") (pintype "passive"))
      (node (ref "C19") (pin "2") (pinfunction "P$2_2") (pintype "passive"))
      (node (ref "C2") (pin "2") (pinfunction "P$2_2") (pintype "passive"))
      (node (ref "C20") (pin "2") (pinfunction "P$2_2") (pintype "passive"))
      (node (ref "C21") (pin "2") (pinfunction "P$2_2") (pintype "passive"))
      (node (ref "C22") (pin "2") (pinfunction "P$2_2") (pintype "passive"))
      (node (ref "C23") (pin "2") (pinfunction "P$2_2") (pintype "passive"))
      (node (ref "C24") (pin "2") (pinfunction "P$2_2") (pintype "passive"))
      (node (ref "C3") (pin "2") (pinfunction "P$2_2") (pintype "passive"))
      (node (ref "C4") (pin "2") (pinfunction "P$2_2") (pintype "passive"))
      (node (ref "C5") (pin "2") (pinfunction "P$2_2") (pintype "passive"))
      (node (ref "C6") (pin "2") (pinfunction "-_2") (pintype "passive"))
      (node (ref "C7") (pin "2") (pinfunction "-_2") (pintype "passive"))
      (node (ref "C8") (pin "2") (pinfunction "P$2_2") (pintype "passive"))
      (node (ref "C9") (pin "2") (pinfunction "-_2") (pintype "passive"))
      (node (ref "CN1") (pin "GND") (pinfunction "GND_GND") (pintype "power_in"))
      (node (ref "CN1") (pin "GNDBREAK") (pinfunction "GNDBREAK_GNDBREAK") (pintype "power_in"))
      (node (ref "J1") (pin "29") (pinfunction "GND_29") (pintype "power_in"))
      (node (ref "J1") (pin "3") (pinfunction "GND_3") (pintype "power_in"))
      (node (ref "J1") (pin "36") (pinfunction "GND_36") (pintype "power_in"))
      (node (ref "J2") (pin "2") (pinfunction "GND_2") (pintype "power_in"))
      (node (ref "J3") (pin "10") (pinfunction "10_10") (pintype "passive"))
      (node (ref "J3") (pin "2") (pinfunction "2_2") (pintype "passive"))
      (node (ref "J4") (pin "10") (pinfunction "10_10") (pintype "passive"))
      (node (ref "J4") (pin "2") (pinfunction "2_2") (pintype "passive"))
      (node (ref "J5") (pin "4") (pinfunction "4_4") (pintype "passive"))
      (node (ref "OSC1") (pin "2") (pinfunction "GND_2") (pintype "power_in"))
      (node (ref "R1") (pin "1") (pinfunction "1_1") (pintype "passive"))
      (node (ref "R14") (pin "1") (pinfunction "1_1") (pintype "passive"))
      (node (ref "R17") (pin "1") (pinfunction "1_1") (pintype "passive"))
      (node (ref "R2") (pin "1") (pinfunction "1_1") (pintype "passive"))
      (node (ref "R3") (pin "1") (pinfunction "1_1") (pintype "passive"))
      (node (ref "R4") (pin "1") (pinfunction "1_1") (pintype "passive"))
      (node (ref "R9") (pin "1") (pinfunction "1_1") (pintype "passive"))
      (node (ref "U1") (pin "12") (pinfunction "VSS_2_12") (pintype "power_in"))
      (node (ref "U1") (pin "34") (pinfunction "VSS_34") (pintype "power_in"))
      (node (ref "U2") (pin "105") (pinfunction "GND_12_105") (pintype "passive"))
      (node (ref "U2") (pin "106") (pinfunction "GND_PLL2_2_106") (pintype "passive"))
      (node (ref "U2") (pin "108") (pinfunction "GND_PLL2_108") (pintype "passive"))
      (node (ref "U2") (pin "110") (pinfunction "GNDA_PLL2_110") (pintype "passive"))
      (node (ref "U2") (pin "111") (pinfunction "GND_13_111") (pintype "passive"))
      (node (ref "U2") (pin "117") (pinfunction "GND_14_117") (pintype "passive"))
      (node (ref "U2") (pin "123") (pinfunction "GND_15_123") (pintype "passive"))
      (node (ref "U2") (pin "128") (pinfunction "GND_16_128") (pintype "passive"))
      (node (ref "U2") (pin "130") (pinfunction "GND_17_130") (pintype "passive"))
      (node (ref "U2") (pin "140") (pinfunction "GND_140") (pintype "passive"))
      (node (ref "U2") (pin "17") (pinfunction "CLK0_17") (pintype "passive"))
      (node (ref "U2") (pin "18") (pinfunction "CLK1_18") (pintype "passive"))
      (node (ref "U2") (pin "19") (pinfunction "GND_3_19") (pintype "passive"))
      (node (ref "U2") (pin "21") (pinfunction "CLK2_21") (pintype "passive"))
      (node (ref "U2") (pin "22") (pinfunction "CLK3_22") (pintype "passive"))
      (node (ref "U2") (pin "33") (pinfunction "GND_4_33") (pintype "passive"))
      (node (ref "U2") (pin "34") (pinfunction "GND_PLL1_2_34") (pintype "passive"))
      (node (ref "U2") (pin "36") (pinfunction "GND_PLL1_36") (pintype "passive"))
      (node (ref "U2") (pin "38") (pinfunction "GNDA_PLL1_38") (pintype "passive"))
      (node (ref "U2") (pin "39") (pinfunction "GND_5_39") (pintype "passive"))
      (node (ref "U2") (pin "49") (pinfunction "GND_6_49") (pintype "passive"))
      (node (ref "U2") (pin "56") (pinfunction "GND_7_56") (pintype "passive"))
      (node (ref "U2") (pin "6") (pinfunction "GND_2_6") (pintype "passive"))
      (node (ref "U2") (pin "61") (pinfunction "GND_8_61") (pintype "passive"))
      (node (ref "U2") (pin "68") (pinfunction "GND_9_68") (pintype "passive"))
      (node (ref "U2") (pin "78") (pinfunction "GND_10_78") (pintype "passive"))
      (node (ref "U2") (pin "84") (pinfunction "MSEL1_84") (pintype "passive"))
      (node (ref "U2") (pin "85") (pinfunction "MSEL0_85") (pintype "passive"))
      (node (ref "U2") (pin "89") (pinfunction "CLK6_89") (pintype "passive"))
      (node (ref "U2") (pin "90") (pinfunction "CLK5_90") (pintype "passive"))
      (node (ref "U2") (pin "91") (pinfunction "CLK4_91") (pintype "passive"))
      (node (ref "U2") (pin "98") (pinfunction "GND_11_98") (pintype "passive"))
      (node (ref "U3") (pin "2") (pinfunction "GND_2") (pintype "bidirectional"))
      (node (ref "U4") (pin "1") (pinfunction "GND_1") (pintype "power_in"))
      (node (ref "U5") (pin "5") (pinfunction "GND/TAB_5") (pintype "power_in"))
      (node (ref "U6") (pin "4") (pinfunction "GND_4") (pintype "power_in"))
    )
    (net (code "102") (name "HSD") (class "Default")
      (node (ref "J1") (pin "32") (pinfunction "HSD_32") (pintype "input"))
      (node (ref "U2") (pin "63") (pinfunction "IO_33_63") (pintype "passive"))
    )
    (net (code "103") (name "INIT_DONE") (class "Default")
      (node (ref "LED4") (pin "A") (pinfunction "A_A") (pintype "passive"))
      (node (ref "U2") (pin "135") (pinfunction "IO_75_135") (pintype "passive"))
    )
    (net (code "104") (name "INTN") (class "Default")
      (node (ref "J2") (pin "5") (pinfunction "INTN_5") (pintype "output"))
      (node (ref "U2") (pin "65") (pinfunction "IO_35_65") (pintype "passive"))
    )
    (net (code "105") (name "JTAG_TCK") (class "Default")
      (node (ref "J4") (pin "1") (pinfunction "1_1") (pintype "passive"))
      (node (ref "R7") (pin "2") (pinfunction "2_2") (pintype "passive"))
    )
    (net (code "106") (name "JTAG_TDI") (class "Default")
      (node (ref "J4") (pin "9") (pinfunction "9_9") (pintype "passive"))
      (node (ref "R16") (pin "1") (pinfunction "1_1") (pintype "passive"))
      (node (ref "U2") (pin "13") (pinfunction "TDI_13") (pintype "passive"))
    )
    (net (code "107") (name "JTAG_TDO") (class "Default")
      (node (ref "J4") (pin "3") (pinfunction "3_3") (pintype "passive"))
      (node (ref "U2") (pin "10") (pinfunction "TDO_10") (pintype "passive"))
    )
    (net (code "108") (name "JTAG_TMS") (class "Default")
      (node (ref "J4") (pin "5") (pinfunction "5_5") (pintype "passive"))
      (node (ref "R15") (pin "1") (pinfunction "1_1") (pintype "passive"))
      (node (ref "U2") (pin "11") (pinfunction "TMS_11") (pintype "passive"))
    )
    (net (code "109") (name "LCDCLK") (class "Default")
      (node (ref "J1") (pin "30") (pinfunction "CLKIN_30") (pintype "input"))
      (node (ref "U2") (pin "9") (pinfunction "IO_8_9") (pintype "passive"))
    )
    (net (code "110") (name "LED+") (class "Default")
      (node (ref "C3") (pin "1") (pinfunction "P$1_1") (pintype "passive"))
      (node (ref "D1") (pin "1") (pinfunction "C_1") (pintype "passive"))
      (node (ref "D2") (pin "C") (pinfunction "C_C") (pintype "passive"))
      (node (ref "J1") (pin "2") (pinfunction "LED+_2") (pintype "power_in"))
    )
    (net (code "111") (name "LED-") (class "Default")
      (node (ref "C4") (pin "1") (pinfunction "P$1_1") (pintype "passive"))
      (node (ref "D1") (pin "2") (pinfunction "A_2") (pintype "passive"))
      (node (ref "J1") (pin "1") (pinfunction "LED-_1") (pintype "power_in"))
      (node (ref "R1") (pin "2") (pinfunction "2_2") (pintype "passive"))
      (node (ref "U3") (pin "3") (pinfunction "FB_3") (pintype "bidirectional"))
    )
    (net (code "112") (name "LIGHT") (class "Default")
      (node (ref "U2") (pin "144") (pinfunction "IO_144") (pintype "passive"))
      (node (ref "U3") (pin "4") (pinfunction "SHDN_4") (pintype "bidirectional"))
    )
    (net (code "113") (name "Net-(C2-P$1)") (class "Default")
      (node (ref "C2") (pin "1") (pinfunction "P$1_1") (pintype "passive"))
      (node (ref "L1") (pin "2") (pinfunction "2_2") (pintype "passive"))
      (node (ref "SJ1") (pin "2") (pinfunction "2_2") (pintype "passive"))
      (node (ref "U3") (pin "5") (pinfunction "VIN_5") (pintype "bidirectional"))
    )
    (net (code "114") (name "Net-(C14-P$1)") (class "Default")
      (node (ref "C14") (pin "1") (pinfunction "P$1_1") (pintype "passive"))
      (node (ref "C15") (pin "1") (pinfunction "+_1") (pintype "passive"))
      (node (ref "FB1") (pin "2") (pinfunction "P$2_2") (pintype "bidirectional"))
      (node (ref "OSC1") (pin "1") (pinfunction "EN_1") (pintype "input"))
      (node (ref "OSC1") (pin "4") (pinfunction "VDD_4") (pintype "power_in"))
    )
    (net (code "115") (name "Net-(CN1-PWR-PadPWR1)") (class "Default")
      (node (ref "CN1") (pin "PWR1") (pinfunction "PWR_PWR1") (pintype "power_in"))
      (node (ref "CN1") (pin "PWR2") (pinfunction "PWR_PWR2") (pintype "power_in"))
      (node (ref "F1") (pin "1") (pinfunction "1_1") (pintype "passive"))
    )
    (net (code "116") (name "Net-(LED1-PadC)") (class "Default")
      (node (ref "LED1") (pin "C") (pinfunction "C_C") (pintype "passive"))
      (node (ref "R3") (pin "2") (pinfunction "2_2") (pintype "passive"))
    )
    (net (code "117") (name "Net-(LED2-PadC)") (class "Default")
      (node (ref "LED2") (pin "C") (pinfunction "C_C") (pintype "passive"))
      (node (ref "R2") (pin "2") (pinfunction "2_2") (pintype "passive"))
    )
    (net (code "118") (name "Net-(LED3-PadC)") (class "Default")
      (node (ref "LED3") (pin "C") (pinfunction "C_C") (pintype "passive"))
      (node (ref "R4") (pin "2") (pinfunction "2_2") (pintype "passive"))
    )
    (net (code "119") (name "Net-(LED4-PadC)") (class "Default")
      (node (ref "LED4") (pin "C") (pinfunction "C_C") (pintype "passive"))
      (node (ref "R17") (pin "2") (pinfunction "2_2") (pintype "passive"))
    )
    (net (code "120") (name "Net-(OSC1-OUT)") (class "Default")
      (node (ref "OSC1") (pin "3") (pinfunction "OUT_3") (pintype "output"))
      (node (ref "R5") (pin "2") (pinfunction "2_2") (pintype "passive"))
    )
    (net (code "121") (name "Net-(U2A-DCLK)") (class "Default")
      (node (ref "R13") (pin "1") (pinfunction "1_1") (pintype "passive"))
      (node (ref "R6") (pin "2") (pinfunction "2_2") (pintype "passive"))
      (node (ref "U2") (pin "15") (pinfunction "DCLK_15") (pintype "passive"))
    )
    (net (code "122") (name "Net-(U2B-TCK)") (class "Default")
      (node (ref "R14") (pin "2") (pinfunction "2_2") (pintype "passive"))
      (node (ref "R7") (pin "1") (pinfunction "1_1") (pintype "passive"))
      (node (ref "U2") (pin "12") (pinfunction "TCK_12") (pintype "passive"))
    )
    (net (code "123") (name "Net-(U3-SW)") (class "Default")
      (node (ref "D2") (pin "A") (pinfunction "A_A") (pintype "passive"))
      (node (ref "L1") (pin "1") (pinfunction "1_1") (pintype "passive"))
      (node (ref "U3") (pin "1") (pinfunction "SW_1") (pintype "bidirectional"))
    )
    (net (code "124") (name "R0") (class "Default")
      (node (ref "J1") (pin "5") (pinfunction "R0_5") (pintype "input"))
      (node (ref "U2") (pin "60") (pinfunction "IO_32_60") (pintype "passive"))
    )
    (net (code "125") (name "R1") (class "Default")
      (node (ref "J1") (pin "6") (pinfunction "R1_6") (pintype "input"))
      (node (ref "U2") (pin "59") (pinfunction "IO_31_59") (pintype "passive"))
    )
    (net (code "126") (name "R2") (class "Default")
      (node (ref "J1") (pin "7") (pinfunction "R2_7") (pintype "input"))
      (node (ref "U2") (pin "58") (pinfunction "IO_30_58") (pintype "passive"))
    )
    (net (code "127") (name "R3") (class "Default")
      (node (ref "J1") (pin "8") (pinfunction "R3_8") (pintype "input"))
      (node (ref "U2") (pin "57") (pinfunction "IO_29_57") (pintype "passive"))
    )
    (net (code "128") (name "R4") (class "Default")
      (node (ref "J1") (pin "9") (pinfunction "R4_9") (pintype "input"))
      (node (ref "U2") (pin "55") (pinfunction "IO_28_55") (pintype "passive"))
    )
    (net (code "129") (name "R5") (class "Default")
      (node (ref "J1") (pin "10") (pinfunction "R5_10") (pintype "input"))
      (node (ref "U2") (pin "53") (pinfunction "IO_27_53") (pintype "passive"))
    )
    (net (code "130") (name "R6") (class "Default")
      (node (ref "J1") (pin "11") (pinfunction "R6_11") (pintype "input"))
      (node (ref "U2") (pin "52") (pinfunction "IO_26_52") (pintype "passive"))
    )
    (net (code "131") (name "R7") (class "Default")
      (node (ref "J1") (pin "12") (pinfunction "R7_12") (pintype "input"))
      (node (ref "U2") (pin "51") (pinfunction "IO_25_51") (pintype "passive"))
    )
    (net (code "132") (name "RSTN") (class "Default")
      (node (ref "J2") (pin "6") (pinfunction "RSTN_6") (pintype "input"))
      (node (ref "U2") (pin "137") (pinfunction "IO_77_137") (pintype "passive"))
    )
    (net (code "133") (name "SCL") (class "Default")
      (node (ref "J2") (pin "3") (pinfunction "SCL_3") (pintype "bidirectional"))
      (node (ref "U2") (pin "141") (pinfunction "IO_79_141") (pintype "passive"))
    )
    (net (code "134") (name "SDA") (class "Default")
      (node (ref "J2") (pin "4") (pinfunction "SDA_4") (pintype "bidirectional"))
      (node (ref "U2") (pin "139") (pinfunction "IO_78_139") (pintype "passive"))
    )
    (net (code "135") (name "SRAM_CS_N") (class "Default")
      (node (ref "U1") (pin "6") (pinfunction "~{CS}_6") (pintype "input"))
      (node (ref "U2") (pin "80") (pinfunction "IO_46_80") (pintype "passive"))
    )
    (net (code "136") (name "SRAM_LB_N") (class "Default")
      (node (ref "U1") (pin "39") (pinfunction "~{LB}_39") (pintype "input"))
      (node (ref "U2") (pin "129") (pinfunction "IO_71_129") (pintype "passive"))
    )
    (net (code "137") (name "SRAM_OE_N") (class "Default")
      (node (ref "U1") (pin "41") (pinfunction "~{OE}_41") (pintype "input"))
      (node (ref "U2") (pin "136") (pinfunction "IO_76_136") (pintype "passive"))
    )
    (net (code "138") (name "SRAM_UB_N") (class "Default")
      (node (ref "U1") (pin "40") (pinfunction "~{UB}_40") (pintype "input"))
      (node (ref "U2") (pin "132") (pinfunction "IO_72_132") (pintype "passive"))
    )
    (net (code "139") (name "SRAM_WE_N") (class "Default")
      (node (ref "U1") (pin "17") (pinfunction "~{WE}_17") (pintype "input"))
      (node (ref "U2") (pin "133") (pinfunction "IO_73_133") (pintype "passive"))
    )
    (net (code "140") (name "STATUS_N") (class "Default")
      (node (ref "R11") (pin "1") (pinfunction "1_1") (pintype "passive"))
      (node (ref "TP5") (pin "TP") (pinfunction "TP_TP") (pintype "input"))
      (node (ref "U2") (pin "82") (pinfunction "~{STATUS}_82") (pintype "passive"))
    )
    (net (code "141") (name "STBYB") (class "Default")
      (node (ref "J1") (pin "31") (pinfunction "STBYB_31") (pintype "input"))
      (node (ref "U2") (pin "7") (pinfunction "IO_6_7") (pintype "passive"))
    )
    (net (code "142") (name "UART_RX") (class "Default")
      (node (ref "J5") (pin "3") (pinfunction "3_3") (pintype "passive"))
      (node (ref "U2") (pin "143") (pinfunction "IO_81_143") (pintype "passive"))
    )
    (net (code "143") (name "UART_TX") (class "Default")
      (node (ref "J5") (pin "2") (pinfunction "2_2") (pintype "passive"))
      (node (ref "U2") (pin "142") (pinfunction "IO_80_142") (pintype "passive"))
    )
    (net (code "144") (name "USRLED1") (class "Default")
      (node (ref "LED1") (pin "A") (pinfunction "A_A") (pintype "passive"))
      (node (ref "U2") (pin "3") (pinfunction "IO_4_3") (pintype "passive"))
    )
    (net (code "145") (name "USRLED2") (class "Default")
      (node (ref "LED2") (pin "A") (pinfunction "A_A") (pintype "passive"))
      (node (ref "U2") (pin "4") (pinfunction "IO_5_4") (pintype "passive"))
    )
    (net (code "146") (name "VIN") (class "Default")
      (node (ref "C8") (pin "1") (pinfunction "P$1_1") (pintype "passive"))
      (node (ref "F1") (pin "2") (pinfunction "2_2") (pintype "passive"))
      (node (ref "SJ1") (pin "1") (pinfunction "1_1") (pintype "passive"))
      (node (ref "U5") (pin "1") (pinfunction "SD_N_1") (pintype "input"))
      (node (ref "U5") (pin "2") (pinfunction "VIN_2") (pintype "power_in"))
    )
    (net (code "147") (name "VSD") (class "Default")
      (node (ref "J1") (pin "33") (pinfunction "VSD_33") (pintype "input"))
      (node (ref "U2") (pin "64") (pinfunction "IO_34_64") (pintype "passive"))
    )
    (net (code "148") (name "unconnected-(J1-NC-Pad35)") (class "Default")
      (node (ref "J1") (pin "35") (pinfunction "NC_35") (pintype "no_connect"))
    )
    (net (code "149") (name "unconnected-(J1-NC-Pad37)") (class "Default")
      (node (ref "J1") (pin "37") (pinfunction "NC_37") (pintype "no_connect"))
    )
    (net (code "150") (name "unconnected-(J1-NC-Pad38)") (class "Default")
      (node (ref "J1") (pin "38") (pinfunction "NC_38") (pintype "no_connect"))
    )
    (net (code "151") (name "unconnected-(J1-NC-Pad39)") (class "Default")
      (node (ref "J1") (pin "39") (pinfunction "NC_39") (pintype "no_connect"))
    )
    (net (code "152") (name "unconnected-(J1-NC-Pad40)") (class "Default")
      (node (ref "J1") (pin "40") (pinfunction "NC_40") (pintype "no_connect"))
    )
    (net (code "153") (name "unconnected-(J4-Pad6)") (class "Default")
      (node (ref "J4") (pin "6") (pinfunction "6_6") (pintype "passive"))
    )
    (net (code "154") (name "unconnected-(J4-Pad7)") (class "Default")
      (node (ref "J4") (pin "7") (pinfunction "7_7") (pintype "passive"))
    )
    (net (code "155") (name "unconnected-(J4-Pad8)") (class "Default")
      (node (ref "J4") (pin "8") (pinfunction "8_8") (pintype "passive"))
    )
  )
)
